# DSO_Front.net
KiCad netlist of a schematic drawn in Altium Designer
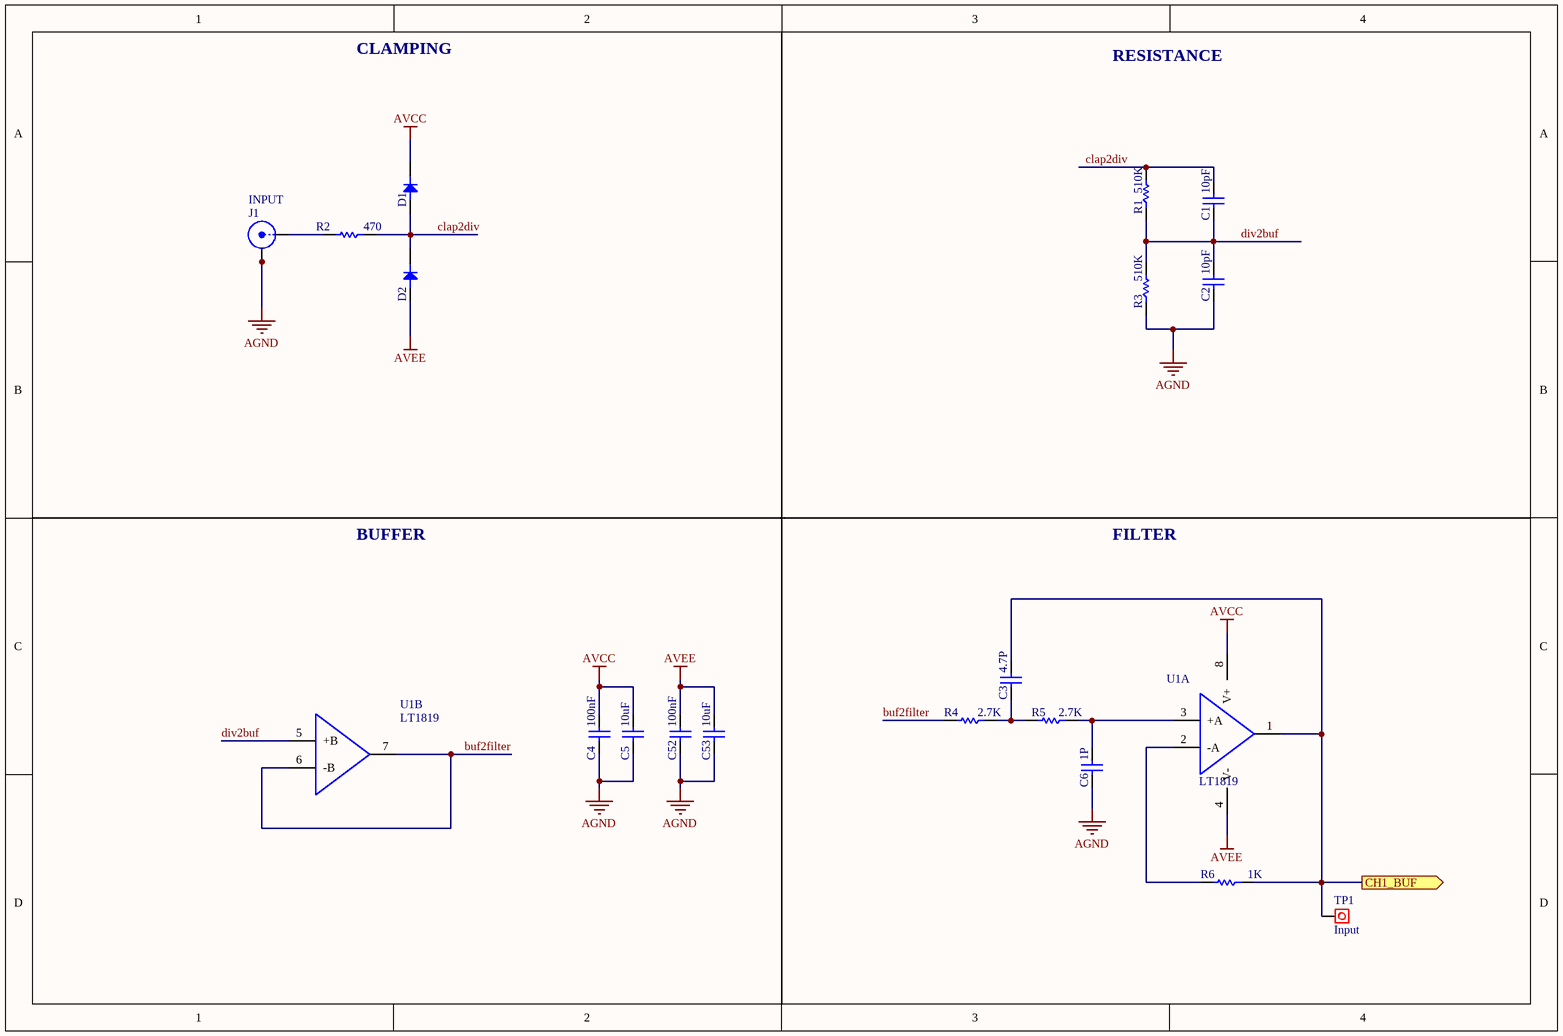
[diagram p0: DSO_Front.SchDoc]

(export (version "E")
  (design (tool "Eeschema 10.0.6"))
  (components
    (comp (ref "C1")
      (value "10pF")
      (footprint "0805C")
      (description "Capacitor")
      (fields (field (name "REVIEWED BY") "RM - 2018/08/05"))
      (libsource (lib "DSO") (part "C"))
    )
    (comp (ref "C2")
      (value "10pF")
      (footprint "0805C")
      (description "Capacitor")
      (fields (field (name "REVIEWED BY") "RM - 2018/08/05"))
      (libsource (lib "DSO") (part "C"))
    )
    (comp (ref "C3")
      (value "4.7P")
      (footprint "0805C")
      (description "Capacitor")
      (fields (field (name "REVIEWED BY") "RM - 2018/08/05"))
      (libsource (lib "DSO") (part "C"))
    )
    (comp (ref "C4")
      (value "100nF")
      (footprint "0805C")
      (description "Capacitor")
      (fields (field (name "REVIEWED BY") "RM - 2018/08/05"))
      (libsource (lib "DSO") (part "C"))
    )
    (comp (ref "C5")
      (value "10uF")
      (footprint "0805C")
      (description "Capacitor")
      (fields (field (name "REVIEWED BY") "RM - 2018/08/05"))
      (libsource (lib "DSO") (part "C"))
    )
    (comp (ref "C6")
      (value "1P")
      (footprint "0805C")
      (description "Capacitor")
      (fields (field (name "REVIEWED BY") "RM - 2018/08/05"))
      (libsource (lib "DSO") (part "C"))
    )
    (comp (ref "C52")
      (value "100nF")
      (footprint "0805C")
      (description "Capacitor")
      (fields (field (name "REVIEWED BY") "RM - 2018/08/05"))
      (libsource (lib "DSO") (part "C"))
    )
    (comp (ref "C53")
      (value "10uF")
      (footprint "0805C")
      (description "Capacitor")
      (fields (field (name "REVIEWED BY") "RM - 2018/08/05"))
      (libsource (lib "DSO") (part "C"))
    )
    (comp (ref "D1")
      (value "Diode")
      (footprint "SOD-123")
      (fields (field (name "REVIEWED BY") "RM - 2018/08/05"))
      (libsource (lib "DSO") (part "D"))
    )
    (comp (ref "D2")
      (value "Diode")
      (footprint "SOD-123")
      (fields (field (name "REVIEWED BY") "RM - 2018/08/05"))
      (libsource (lib "DSO") (part "D"))
    )
    (comp (ref "J1")
      (value "INPUT")
      (footprint "BNC_VERT")
      (description "BNC Straight")
      (fields (field (name "REVIEWED BY") "RM - 2018/08/05"))
      (libsource (lib "DSO") (part "BNC"))
    )
    (comp (ref "R1")
      (value "510K")
      (footprint "0805")
      (description "Resistor")
      (fields (field (name "REVIEWED BY") "RM - 2018/08/05"))
      (libsource (lib "DSO") (part "R"))
    )
    (comp (ref "R2")
      (value "470")
      (footprint "0805")
      (description "Resistor")
      (fields (field (name "REVIEWED BY") "RM - 2018/08/05"))
      (libsource (lib "DSO") (part "R"))
    )
    (comp (ref "R3")
      (value "510K")
      (footprint "0805")
      (description "Resistor")
      (fields (field (name "REVIEWED BY") "RM - 2018/08/05"))
      (libsource (lib "DSO") (part "R"))
    )
    (comp (ref "R4")
      (value "2.7K")
      (footprint "0805")
      (description "Resistor")
      (fields (field (name "REVIEWED BY") "RM - 2018/08/05"))
      (libsource (lib "DSO") (part "R"))
    )
    (comp (ref "R5")
      (value "2.7K")
      (footprint "0805")
      (description "Resistor")
      (fields (field (name "REVIEWED BY") "RM - 2018/08/05"))
      (libsource (lib "DSO") (part "R"))
    )
    (comp (ref "R6")
      (value "1K")
      (footprint "0805")
      (description "Resistor")
      (fields (field (name "REVIEWED BY") "RM - 2018/08/05"))
      (libsource (lib "DSO") (part "R"))
    )
    (comp (ref "TP1")
      (value "Input")
      (footprint "Testpoin")
      (description "Pad")
      (fields (field (name "Comment") "INPUT"))
      (libsource (lib "DSO") (part "Test Point"))
    )
    (comp (ref "U1")
      (value "LT1819")
      (footprint "SOIC-8")
      (description "OpAmp High Frequency Dual")
      (fields (field (name "REVIEWED BY") "RM - 2018/08/05"))
      (libsource (lib "DSO") (part "LT1819"))
    )
  )
  (nets
    (net (code "1") (name "/CH1_BUF") (class "Default")
      (node (ref "C3") (pin "1") (pinfunction "1_1") (pintype "passive"))
      (node (ref "R6") (pin "1") (pintype "passive"))
      (node (ref "TP1") (pin "1") (pintype "passive"))
      (node (ref "U1") (pin "1") (pinfunction "OUTA_1") (pintype "passive"))
    )
    (net (code "2") (name "/buf2filter") (class "Default")
      (node (ref "R4") (pin "2") (pintype "passive"))
      (node (ref "U1") (pin "6") (pinfunction "-B_6") (pintype "passive"))
      (node (ref "U1") (pin "7") (pinfunction "OUTB_7") (pintype "passive"))
    )
    (net (code "3") (name "/clap2div") (class "Default")
      (node (ref "C1") (pin "1") (pinfunction "1_1") (pintype "passive"))
      (node (ref "D1") (pin "A") (pinfunction "A_A") (pintype "passive"))
      (node (ref "D2") (pin "K") (pinfunction "K_K") (pintype "passive"))
      (node (ref "R1") (pin "2") (pintype "passive"))
      (node (ref "R2") (pin "1") (pintype "passive"))
    )
    (net (code "4") (name "/div2buf") (class "Default")
      (node (ref "C1") (pin "2") (pinfunction "2_2") (pintype "passive"))
      (node (ref "C2") (pin "1") (pinfunction "1_1") (pintype "passive"))
      (node (ref "R1") (pin "1") (pintype "passive"))
      (node (ref "R3") (pin "2") (pintype "passive"))
      (node (ref "U1") (pin "5") (pinfunction "+B_5") (pintype "passive"))
    )
    (net (code "5") (name "AGND") (class "Default")
      (node (ref "C2") (pin "2") (pinfunction "2_2") (pintype "passive"))
      (node (ref "C4") (pin "2") (pinfunction "2_2") (pintype "passive"))
      (node (ref "C5") (pin "2") (pinfunction "2_2") (pintype "passive"))
      (node (ref "C52") (pin "2") (pinfunction "2_2") (pintype "passive"))
      (node (ref "C53") (pin "2") (pinfunction "2_2") (pintype "passive"))
      (node (ref "C6") (pin "2") (pinfunction "2_2") (pintype "passive"))
      (node (ref "J1") (pin "2") (pinfunction "Y_2") (pintype "passive"))
      (node (ref "J1") (pin "3") (pinfunction "Y_3") (pintype "passive"))
      (node (ref "J1") (pin "4") (pinfunction "Y_4") (pintype "passive"))
      (node (ref "J1") (pin "5") (pinfunction "Y_5") (pintype "passive"))
      (node (ref "R3") (pin "1") (pintype "passive"))
    )
    (net (code "6") (name "AVCC") (class "Default")
      (node (ref "C4") (pin "1") (pinfunction "1_1") (pintype "passive"))
      (node (ref "C5") (pin "1") (pinfunction "1_1") (pintype "passive"))
      (node (ref "D1") (pin "K") (pinfunction "K_K") (pintype "passive"))
      (node (ref "U1") (pin "8") (pinfunction "V+_8") (pintype "passive"))
    )
    (net (code "7") (name "AVEE") (class "Default")
      (node (ref "C52") (pin "1") (pinfunction "1_1") (pintype "passive"))
      (node (ref "C53") (pin "1") (pinfunction "1_1") (pintype "passive"))
      (node (ref "D2") (pin "A") (pinfunction "A_A") (pintype "passive"))
      (node (ref "U1") (pin "4") (pinfunction "V-_4") (pintype "passive"))
    )
    (net (code "8") (name "Net-(C3-Pad2)") (class "Default")
      (node (ref "C3") (pin "2") (pinfunction "2_2") (pintype "passive"))
      (node (ref "R4") (pin "1") (pintype "passive"))
      (node (ref "R5") (pin "2") (pintype "passive"))
    )
    (net (code "9") (name "Net-(J1-X)") (class "Default")
      (node (ref "J1") (pin "1") (pinfunction "X_1") (pintype "passive"))
      (node (ref "R2") (pin "2") (pintype "passive"))
    )
    (net (code "10") (name "Net-(U1A-+A)") (class "Default")
      (node (ref "C6") (pin "1") (pinfunction "1_1") (pintype "passive"))
      (node (ref "R5") (pin "1") (pintype "passive"))
      (node (ref "U1") (pin "3") (pinfunction "+A_3") (pintype "passive"))
    )
    (net (code "11") (name "Net-(U1A--A)") (class "Default")
      (node (ref "R6") (pin "2") (pintype "passive"))
      (node (ref "U1") (pin "2") (pinfunction "-A_2") (pintype "passive"))
    )
  )
)
